# ina219.net
KiCad netlist of a schematic drawn in Altium Designer
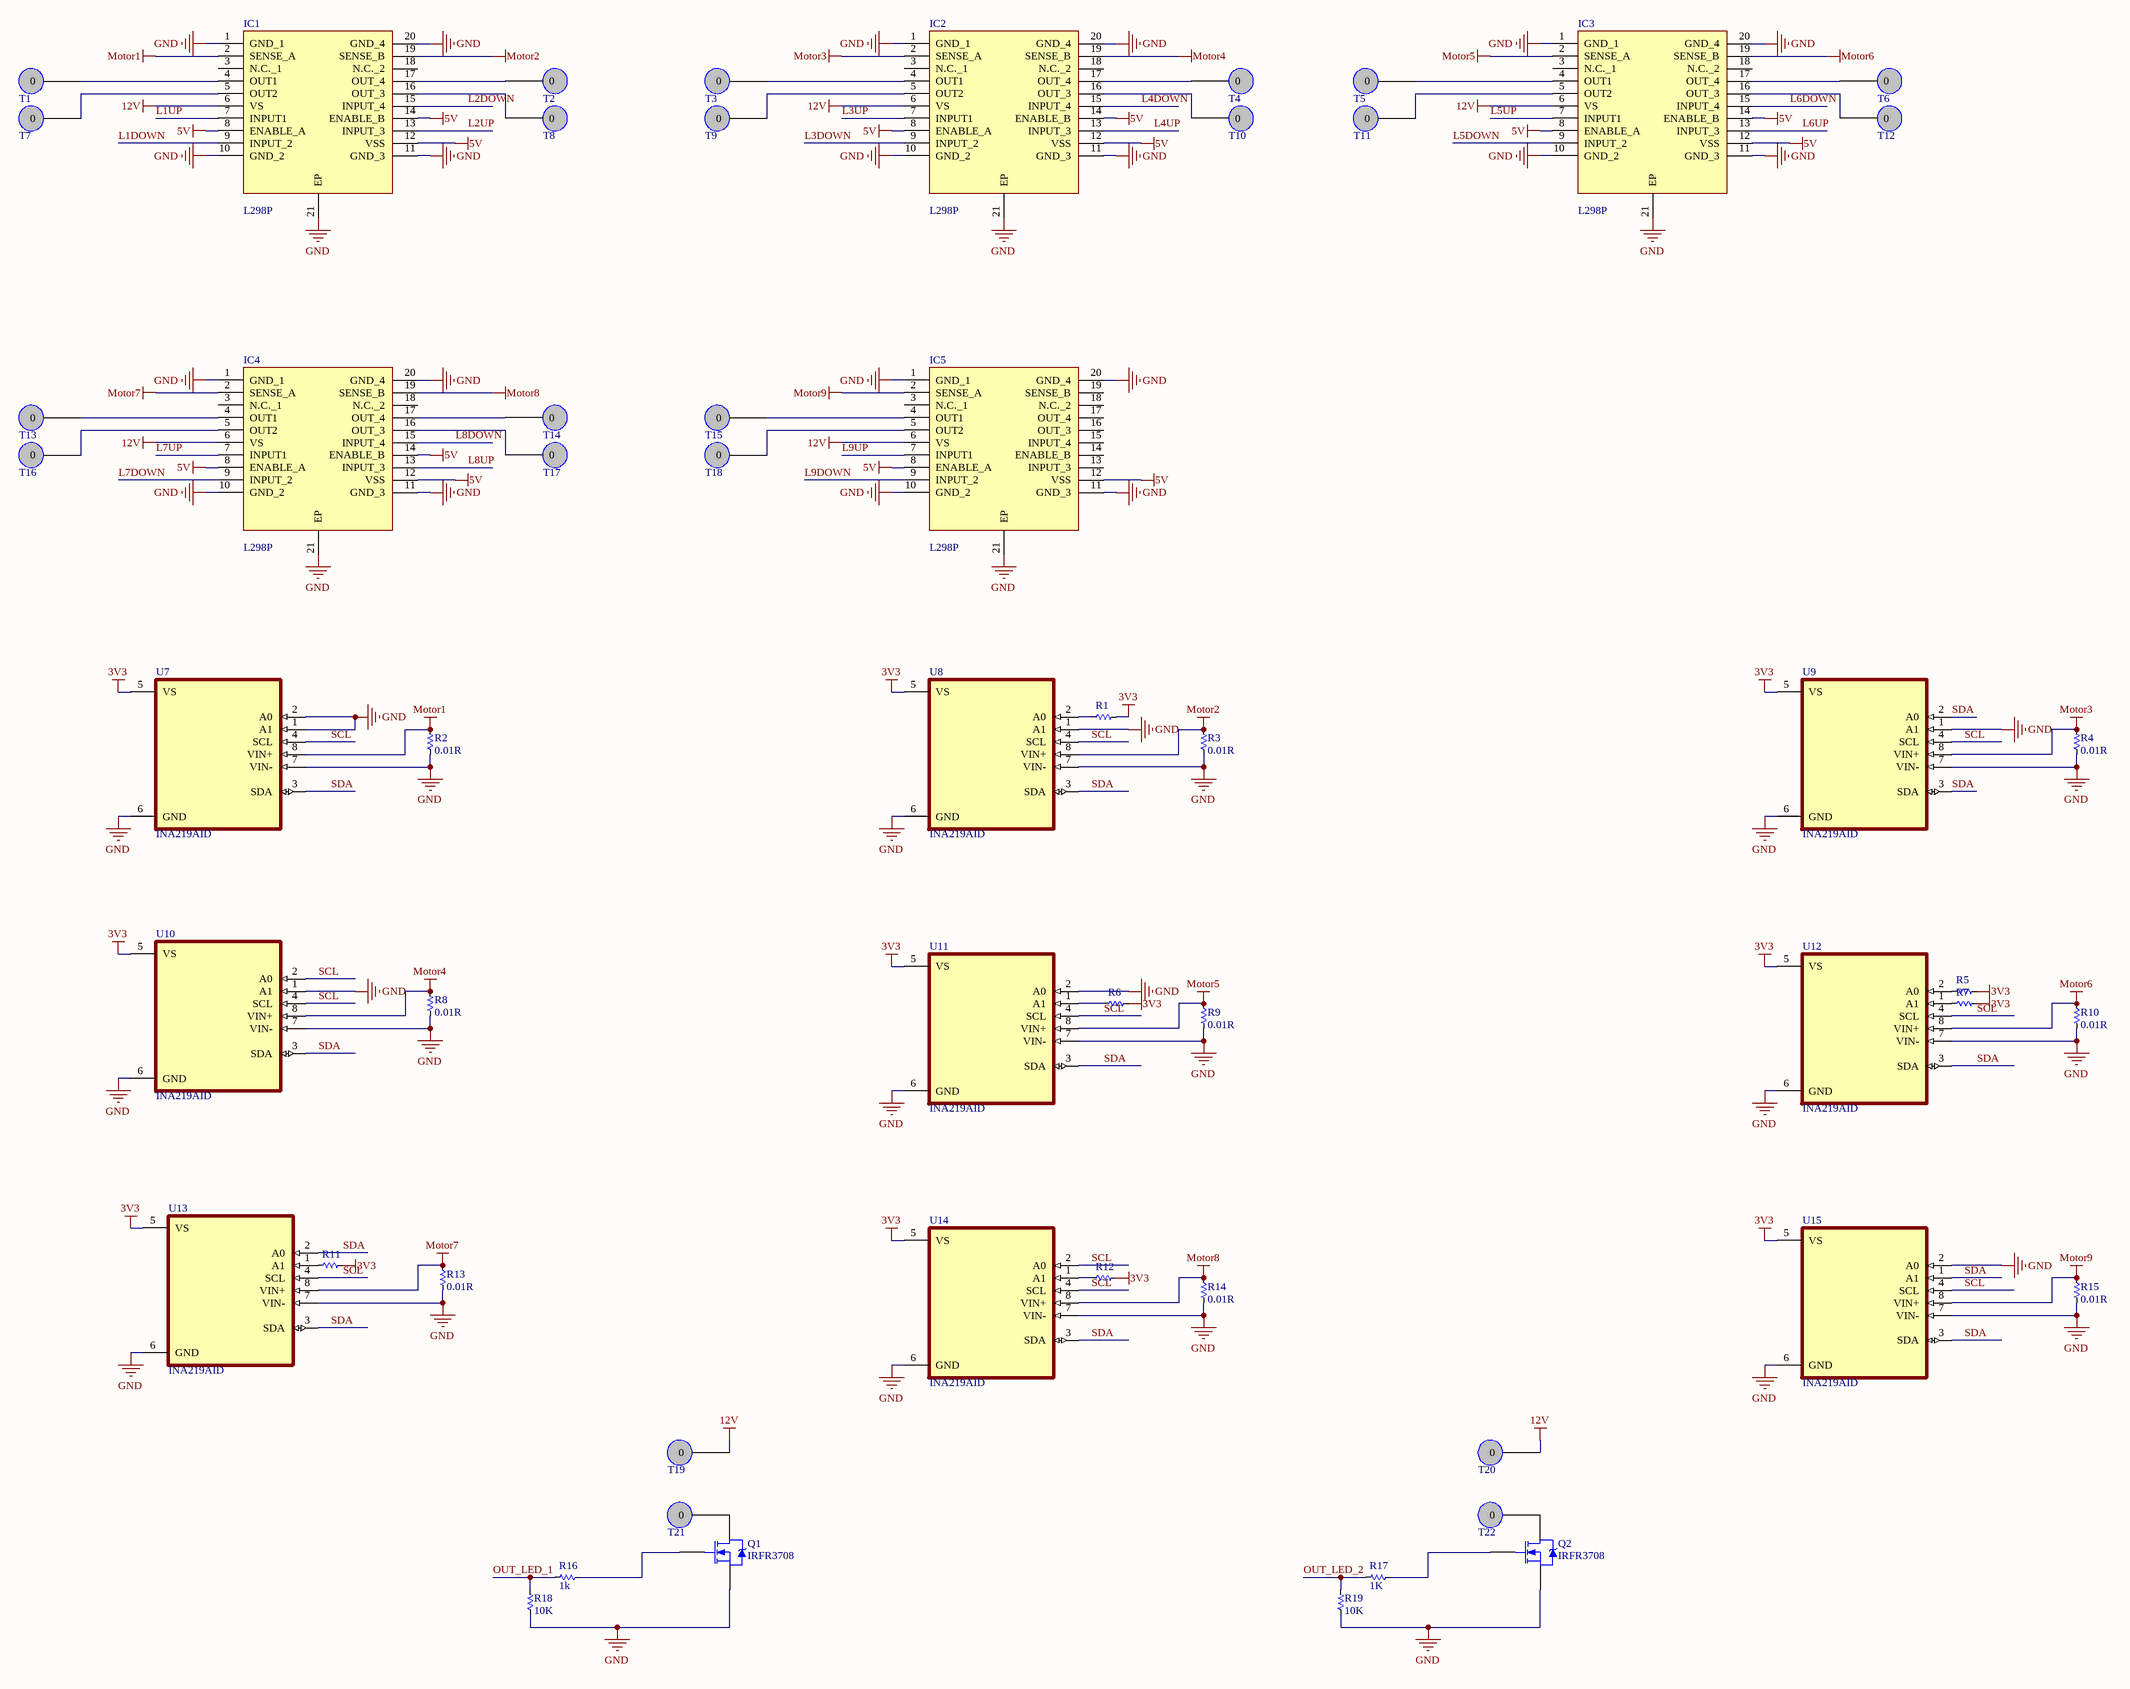
[diagram p0: ina219.SchDoc]

(export (version "E")
  (design (tool "Eeschema 10.0.6"))
  (components
    (comp (ref "IC1")
      (value "L298P")
      (footprint "SamacSys:SOIC127P1420X360-21N")
      (description "Integrated Circuit")
      (fields (field (name "MOUSER PART NUMBER") "511-L298P"))
      (libsource (lib "SamacSys") (part "L298P"))
    )
    (comp (ref "IC2")
      (value "L298P")
      (footprint "SamacSys:SOIC127P1420X360-21N")
      (description "Integrated Circuit")
      (fields (field (name "MOUSER PART NUMBER") "511-L298P"))
      (libsource (lib "SamacSys") (part "L298P"))
    )
    (comp (ref "IC3")
      (value "L298P")
      (footprint "SamacSys:SOIC127P1420X360-21N")
      (description "Integrated Circuit")
      (fields (field (name "MOUSER PART NUMBER") "511-L298P"))
      (libsource (lib "SamacSys") (part "L298P"))
    )
    (comp (ref "IC4")
      (value "L298P")
      (footprint "SamacSys:SOIC127P1420X360-21N")
      (description "Integrated Circuit")
      (fields (field (name "MOUSER PART NUMBER") "511-L298P"))
      (libsource (lib "SamacSys") (part "L298P"))
    )
    (comp (ref "IC5")
      (value "L298P")
      (footprint "SamacSys:SOIC127P1420X360-21N")
      (description "Integrated Circuit")
      (fields (field (name "MOUSER PART NUMBER") "511-L298P"))
      (libsource (lib "SamacSys") (part "L298P"))
    )
    (comp (ref "Q1")
      (value "IRFR3708")
      (footprint "TO-252AA_M")
      (description "HEXFET Power MOSFET")
      (fields (field (name "PUBLISHER") "Altium Limited"))
      (libsource (lib "IR Discrete MOSFET - Power") (part "IRFR3910"))
    )
    (comp (ref "Q2")
      (value "IRFR3708")
      (footprint "TO-252AA_M")
      (description "HEXFET Power MOSFET")
      (fields (field (name "PUBLISHER") "Altium Limited"))
      (libsource (lib "IR Discrete MOSFET - Power") (part "IRFR3910"))
    )
    (comp (ref "R1")
      (value "Res")
      (footprint "RES-SMD-0603")
      (description "Resistor")
      (fields
        (field (name "MANUFACTURER") "Generic Components")
        (field (name "PUBLISHER") "Altium Hobart Technology Centre")
      )
      (libsource (lib "LIBRARY") (part "Res-SMD"))
    )
    (comp (ref "R2")
      (value "0.01R")
      (footprint "RES-SMD-2512")
      (description "Resistor")
      (fields
        (field (name "MANUFACTURER") "Generic Components")
        (field (name "PUBLISHER") "Altium Hobart Technology Centre")
      )
      (libsource (lib "LIBRARY") (part "Res-SMD"))
    )
    (comp (ref "R3")
      (value "0.01R")
      (footprint "RES-SMD-2512")
      (description "Resistor")
      (fields
        (field (name "MANUFACTURER") "Generic Components")
        (field (name "PUBLISHER") "Altium Hobart Technology Centre")
      )
      (libsource (lib "LIBRARY") (part "Res-SMD"))
    )
    (comp (ref "R4")
      (value "0.01R")
      (footprint "RES-SMD-2512")
      (description "Resistor")
      (fields
        (field (name "MANUFACTURER") "Generic Components")
        (field (name "PUBLISHER") "Altium Hobart Technology Centre")
      )
      (libsource (lib "LIBRARY") (part "Res-SMD"))
    )
    (comp (ref "R5")
      (value "Res")
      (footprint "RES-SMD-0603")
      (description "Resistor")
      (fields
        (field (name "MANUFACTURER") "Generic Components")
        (field (name "PUBLISHER") "Altium Hobart Technology Centre")
      )
      (libsource (lib "LIBRARY") (part "Res-SMD"))
    )
    (comp (ref "R6")
      (value "Res")
      (footprint "RES-SMD-0603")
      (description "Resistor")
      (fields
        (field (name "MANUFACTURER") "Generic Components")
        (field (name "PUBLISHER") "Altium Hobart Technology Centre")
      )
      (libsource (lib "LIBRARY") (part "Res-SMD"))
    )
    (comp (ref "R7")
      (value "Res")
      (footprint "RES-SMD-0603")
      (description "Resistor")
      (fields
        (field (name "MANUFACTURER") "Generic Components")
        (field (name "PUBLISHER") "Altium Hobart Technology Centre")
      )
      (libsource (lib "LIBRARY") (part "Res-SMD"))
    )
    (comp (ref "R8")
      (value "0.01R")
      (footprint "RES-SMD-2512")
      (description "Resistor")
      (fields
        (field (name "MANUFACTURER") "Generic Components")
        (field (name "PUBLISHER") "Altium Hobart Technology Centre")
      )
      (libsource (lib "LIBRARY") (part "Res-SMD"))
    )
    (comp (ref "R9")
      (value "0.01R")
      (footprint "RES-SMD-2512")
      (description "Resistor")
      (fields
        (field (name "MANUFACTURER") "Generic Components")
        (field (name "PUBLISHER") "Altium Hobart Technology Centre")
      )
      (libsource (lib "LIBRARY") (part "Res-SMD"))
    )
    (comp (ref "R10")
      (value "0.01R")
      (footprint "RES-SMD-2512")
      (description "Resistor")
      (fields
        (field (name "MANUFACTURER") "Generic Components")
        (field (name "PUBLISHER") "Altium Hobart Technology Centre")
      )
      (libsource (lib "LIBRARY") (part "Res-SMD"))
    )
    (comp (ref "R11")
      (value "Res")
      (footprint "RES-SMD-0603")
      (description "Resistor")
      (fields
        (field (name "MANUFACTURER") "Generic Components")
        (field (name "PUBLISHER") "Altium Hobart Technology Centre")
      )
      (libsource (lib "LIBRARY") (part "Res-SMD"))
    )
    (comp (ref "R12")
      (value "Res")
      (footprint "RES-SMD-0603")
      (description "Resistor")
      (fields
        (field (name "MANUFACTURER") "Generic Components")
        (field (name "PUBLISHER") "Altium Hobart Technology Centre")
      )
      (libsource (lib "LIBRARY") (part "Res-SMD"))
    )
    (comp (ref "R13")
      (value "0.01R")
      (footprint "RES-SMD-2512")
      (description "Resistor")
      (fields
        (field (name "MANUFACTURER") "Generic Components")
        (field (name "PUBLISHER") "Altium Hobart Technology Centre")
      )
      (libsource (lib "LIBRARY") (part "Res-SMD"))
    )
    (comp (ref "R14")
      (value "0.01R")
      (footprint "RES-SMD-2512")
      (description "Resistor")
      (fields
        (field (name "MANUFACTURER") "Generic Components")
        (field (name "PUBLISHER") "Altium Hobart Technology Centre")
      )
      (libsource (lib "LIBRARY") (part "Res-SMD"))
    )
    (comp (ref "R15")
      (value "0.01R")
      (footprint "RES-SMD-2512")
      (description "Resistor")
      (fields
        (field (name "MANUFACTURER") "Generic Components")
        (field (name "PUBLISHER") "Altium Hobart Technology Centre")
      )
      (libsource (lib "LIBRARY") (part "Res-SMD"))
    )
    (comp (ref "R16")
      (value "1k")
      (footprint "RES-SMD-0603")
      (description "Resistor")
      (fields
        (field (name "MANUFACTURER") "Generic Components")
        (field (name "PUBLISHER") "Altium Hobart Technology Centre")
      )
      (libsource (lib "LIBRARY") (part "Res-SMD"))
    )
    (comp (ref "R17")
      (value "1K")
      (footprint "RES-SMD-0603")
      (description "Resistor")
      (fields
        (field (name "MANUFACTURER") "Generic Components")
        (field (name "PUBLISHER") "Altium Hobart Technology Centre")
      )
      (libsource (lib "LIBRARY") (part "Res-SMD"))
    )
    (comp (ref "R18")
      (value "10K")
      (footprint "RES-SMD-0603")
      (description "Resistor")
      (fields
        (field (name "MANUFACTURER") "Generic Components")
        (field (name "PUBLISHER") "Altium Hobart Technology Centre")
      )
      (libsource (lib "LIBRARY") (part "Res-SMD"))
    )
    (comp (ref "R19")
      (value "10K")
      (footprint "RES-SMD-0603")
      (description "Resistor")
      (fields
        (field (name "MANUFACTURER") "Generic Components")
        (field (name "PUBLISHER") "Altium Hobart Technology Centre")
      )
      (libsource (lib "LIBRARY") (part "Res-SMD"))
    )
    (comp (ref "T1")
      (value "Pad")
      (footprint "pad_ina:PCBComponent_1")
      (description "pad")
      (libsource (lib "pad_ina") (part "Component_1"))
    )
    (comp (ref "T2")
      (value "Pad")
      (footprint "pad_ina:PCBComponent_1")
      (description "pad")
      (libsource (lib "pad_ina") (part "Component_1"))
    )
    (comp (ref "T3")
      (value "Pad")
      (footprint "pad_ina:PCBComponent_1")
      (description "pad")
      (libsource (lib "pad_ina") (part "Component_1"))
    )
    (comp (ref "T4")
      (value "Pad")
      (footprint "pad_ina:PCBComponent_1")
      (description "pad")
      (libsource (lib "pad_ina") (part "Component_1"))
    )
    (comp (ref "T5")
      (value "Pad")
      (footprint "pad_ina:PCBComponent_1")
      (description "pad")
      (libsource (lib "pad_ina") (part "Component_1"))
    )
    (comp (ref "T6")
      (value "Pad")
      (footprint "pad_ina:PCBComponent_1")
      (description "pad")
      (libsource (lib "pad_ina") (part "Component_1"))
    )
    (comp (ref "T7")
      (value "Pad")
      (footprint "pad_ina:PCBComponent_1")
      (description "pad")
      (libsource (lib "pad_ina") (part "Component_1"))
    )
    (comp (ref "T8")
      (value "Pad")
      (footprint "pad_ina:PCBComponent_1")
      (description "pad")
      (libsource (lib "pad_ina") (part "Component_1"))
    )
    (comp (ref "T9")
      (value "Pad")
      (footprint "pad_ina:PCBComponent_1")
      (description "pad")
      (libsource (lib "pad_ina") (part "Component_1"))
    )
    (comp (ref "T10")
      (value "Pad")
      (footprint "pad_ina:PCBComponent_1")
      (description "pad")
      (libsource (lib "pad_ina") (part "Component_1"))
    )
    (comp (ref "T11")
      (value "Pad")
      (footprint "pad_ina:PCBComponent_1")
      (description "pad")
      (libsource (lib "pad_ina") (part "Component_1"))
    )
    (comp (ref "T12")
      (value "Pad")
      (footprint "pad_ina:PCBComponent_1")
      (description "pad")
      (libsource (lib "pad_ina") (part "Component_1"))
    )
    (comp (ref "T13")
      (value "Pad")
      (footprint "pad_ina:PCBComponent_1")
      (description "pad")
      (libsource (lib "pad_ina") (part "Component_1"))
    )
    (comp (ref "T14")
      (value "Pad")
      (footprint "pad_ina:PCBComponent_1")
      (description "pad")
      (libsource (lib "pad_ina") (part "Component_1"))
    )
    (comp (ref "T15")
      (value "Pad")
      (footprint "pad_ina:PCBComponent_1")
      (description "pad")
      (libsource (lib "pad_ina") (part "Component_1"))
    )
    (comp (ref "T16")
      (value "Pad")
      (footprint "pad_ina:PCBComponent_1")
      (description "pad")
      (libsource (lib "pad_ina") (part "Component_1"))
    )
    (comp (ref "T17")
      (value "Pad")
      (footprint "pad_ina:PCBComponent_1")
      (description "pad")
      (libsource (lib "pad_ina") (part "Component_1"))
    )
    (comp (ref "T18")
      (value "Pad")
      (footprint "pad_ina:PCBComponent_1")
      (description "pad")
      (libsource (lib "pad_ina") (part "Component_1"))
    )
    (comp (ref "T19")
      (value "Pad")
      (footprint "pad_ina:PCBComponent_1")
      (description "pad")
      (libsource (lib "pad_ina") (part "Component_1"))
    )
    (comp (ref "T20")
      (value "Pad")
      (footprint "pad_ina:PCBComponent_1")
      (description "pad")
      (libsource (lib "pad_ina") (part "Component_1"))
    )
    (comp (ref "T21")
      (value "Pad")
      (footprint "pad_ina:PCBComponent_1")
      (description "pad")
      (libsource (lib "pad_ina") (part "Component_1"))
    )
    (comp (ref "T22")
      (value "Pad")
      (footprint "pad_ina:PCBComponent_1")
      (description "pad")
      (libsource (lib "pad_ina") (part "Component_1"))
    )
    (comp (ref "U7")
      (value "INA219AID")
      (footprint "INA219AID:SOIC127P599X175-8N")
      (description "26V, 12-bit, i2c output current/voltage/power monitor 8-SOIC -40 to 125")
      (fields (field (name "MF") "Texas Instruments"))
      (libsource (lib "INA219AID") (part "INA219AID"))
    )
    (comp (ref "U8")
      (value "INA219AID")
      (footprint "INA219AID:SOIC127P599X175-8N")
      (description "26V, 12-bit, i2c output current/voltage/power monitor 8-SOIC -40 to 125")
      (fields (field (name "MF") "Texas Instruments"))
      (libsource (lib "INA219AID") (part "INA219AID"))
    )
    (comp (ref "U9")
      (value "INA219AID")
      (footprint "INA219AID:SOIC127P599X175-8N")
      (description "26V, 12-bit, i2c output current/voltage/power monitor 8-SOIC -40 to 125")
      (fields (field (name "MF") "Texas Instruments"))
      (libsource (lib "INA219AID") (part "INA219AID"))
    )
    (comp (ref "U10")
      (value "INA219AID")
      (footprint "INA219AID:SOIC127P599X175-8N")
      (description "26V, 12-bit, i2c output current/voltage/power monitor 8-SOIC -40 to 125")
      (fields (field (name "MF") "Texas Instruments"))
      (libsource (lib "INA219AID") (part "INA219AID"))
    )
    (comp (ref "U11")
      (value "INA219AID")
      (footprint "INA219AID:SOIC127P599X175-8N")
      (description "26V, 12-bit, i2c output current/voltage/power monitor 8-SOIC -40 to 125")
      (fields (field (name "MF") "Texas Instruments"))
      (libsource (lib "INA219AID") (part "INA219AID"))
    )
    (comp (ref "U12")
      (value "INA219AID")
      (footprint "INA219AID:SOIC127P599X175-8N")
      (description "26V, 12-bit, i2c output current/voltage/power monitor 8-SOIC -40 to 125")
      (fields (field (name "MF") "Texas Instruments"))
      (libsource (lib "INA219AID") (part "INA219AID"))
    )
    (comp (ref "U13")
      (value "INA219AID")
      (footprint "INA219AID:SOIC127P599X175-8N")
      (description "26V, 12-bit, i2c output current/voltage/power monitor 8-SOIC -40 to 125")
      (fields (field (name "MF") "Texas Instruments"))
      (libsource (lib "INA219AID") (part "INA219AID"))
    )
    (comp (ref "U14")
      (value "INA219AID")
      (footprint "INA219AID:SOIC127P599X175-8N")
      (description "26V, 12-bit, i2c output current/voltage/power monitor 8-SOIC -40 to 125")
      (fields (field (name "MF") "Texas Instruments"))
      (libsource (lib "INA219AID") (part "INA219AID"))
    )
    (comp (ref "U15")
      (value "INA219AID")
      (footprint "INA219AID:SOIC127P599X175-8N")
      (description "26V, 12-bit, i2c output current/voltage/power monitor 8-SOIC -40 to 125")
      (fields (field (name "MF") "Texas Instruments"))
      (libsource (lib "INA219AID") (part "INA219AID"))
    )
  )
  (nets
    (net (code "1") (name "/L1DOWN") (class "Default")
      (node (ref "IC1") (pin "9") (pinfunction "INPUT_2_9") (pintype "passive"))
    )
    (net (code "2") (name "/L1UP") (class "Default")
      (node (ref "IC1") (pin "7") (pinfunction "INPUT1_7") (pintype "passive"))
    )
    (net (code "3") (name "/L2DOWN") (class "Default")
      (node (ref "IC1") (pin "15") (pinfunction "INPUT_4_15") (pintype "passive"))
    )
    (net (code "4") (name "/L2UP") (class "Default")
      (node (ref "IC1") (pin "13") (pinfunction "INPUT_3_13") (pintype "passive"))
    )
    (net (code "5") (name "/L3DOWN") (class "Default")
      (node (ref "IC2") (pin "9") (pinfunction "INPUT_2_9") (pintype "passive"))
    )
    (net (code "6") (name "/L3UP") (class "Default")
      (node (ref "IC2") (pin "7") (pinfunction "INPUT1_7") (pintype "passive"))
    )
    (net (code "7") (name "/L4DOWN") (class "Default")
      (node (ref "IC2") (pin "15") (pinfunction "INPUT_4_15") (pintype "passive"))
    )
    (net (code "8") (name "/L4UP") (class "Default")
      (node (ref "IC2") (pin "13") (pinfunction "INPUT_3_13") (pintype "passive"))
    )
    (net (code "9") (name "/L5DOWN") (class "Default")
      (node (ref "IC3") (pin "9") (pinfunction "INPUT_2_9") (pintype "passive"))
    )
    (net (code "10") (name "/L5UP") (class "Default")
      (node (ref "IC3") (pin "7") (pinfunction "INPUT1_7") (pintype "passive"))
    )
    (net (code "11") (name "/L6DOWN") (class "Default")
      (node (ref "IC3") (pin "15") (pinfunction "INPUT_4_15") (pintype "passive"))
    )
    (net (code "12") (name "/L6UP") (class "Default")
      (node (ref "IC3") (pin "13") (pinfunction "INPUT_3_13") (pintype "passive"))
    )
    (net (code "13") (name "/L7DOWN") (class "Default")
      (node (ref "IC4") (pin "9") (pinfunction "INPUT_2_9") (pintype "passive"))
    )
    (net (code "14") (name "/L7UP") (class "Default")
      (node (ref "IC4") (pin "7") (pinfunction "INPUT1_7") (pintype "passive"))
    )
    (net (code "15") (name "/L8DOWN") (class "Default")
      (node (ref "IC4") (pin "15") (pinfunction "INPUT_4_15") (pintype "passive"))
    )
    (net (code "16") (name "/L8UP") (class "Default")
      (node (ref "IC4") (pin "13") (pinfunction "INPUT_3_13") (pintype "passive"))
    )
    (net (code "17") (name "/L9DOWN") (class "Default")
      (node (ref "IC5") (pin "9") (pinfunction "INPUT_2_9") (pintype "passive"))
    )
    (net (code "18") (name "/L9UP") (class "Default")
      (node (ref "IC5") (pin "7") (pinfunction "INPUT1_7") (pintype "passive"))
    )
    (net (code "19") (name "/OUT_LED_1") (class "Default")
      (node (ref "R16") (pin "1") (pinfunction "1_1") (pintype "passive"))
      (node (ref "R18") (pin "1") (pinfunction "1_1") (pintype "passive"))
    )
    (net (code "20") (name "/OUT_LED_2") (class "Default")
      (node (ref "R17") (pin "1") (pinfunction "1_1") (pintype "passive"))
      (node (ref "R19") (pin "1") (pinfunction "1_1") (pintype "passive"))
    )
    (net (code "21") (name "/SCL") (class "Default")
      (node (ref "U10") (pin "2") (pinfunction "A0_2") (pintype "input"))
      (node (ref "U10") (pin "4") (pinfunction "SCL_4") (pintype "input"))
      (node (ref "U11") (pin "4") (pinfunction "SCL_4") (pintype "input"))
      (node (ref "U12") (pin "4") (pinfunction "SCL_4") (pintype "input"))
      (node (ref "U13") (pin "4") (pinfunction "SCL_4") (pintype "input"))
      (node (ref "U14") (pin "2") (pinfunction "A0_2") (pintype "input"))
      (node (ref "U14") (pin "4") (pinfunction "SCL_4") (pintype "input"))
      (node (ref "U15") (pin "4") (pinfunction "SCL_4") (pintype "input"))
      (node (ref "U7") (pin "4") (pinfunction "SCL_4") (pintype "input"))
      (node (ref "U8") (pin "4") (pinfunction "SCL_4") (pintype "input"))
      (node (ref "U9") (pin "4") (pinfunction "SCL_4") (pintype "input"))
    )
    (net (code "22") (name "/SDA") (class "Default")
      (node (ref "U10") (pin "3") (pinfunction "SDA_3") (pintype "bidirectional"))
      (node (ref "U11") (pin "3") (pinfunction "SDA_3") (pintype "bidirectional"))
      (node (ref "U12") (pin "3") (pinfunction "SDA_3") (pintype "bidirectional"))
      (node (ref "U13") (pin "2") (pinfunction "A0_2") (pintype "input"))
      (node (ref "U13") (pin "3") (pinfunction "SDA_3") (pintype "bidirectional"))
      (node (ref "U14") (pin "3") (pinfunction "SDA_3") (pintype "bidirectional"))
      (node (ref "U15") (pin "1") (pinfunction "A1_1") (pintype "input"))
      (node (ref "U15") (pin "3") (pinfunction "SDA_3") (pintype "bidirectional"))
      (node (ref "U7") (pin "3") (pinfunction "SDA_3") (pintype "bidirectional"))
      (node (ref "U8") (pin "3") (pinfunction "SDA_3") (pintype "bidirectional"))
      (node (ref "U9") (pin "2") (pinfunction "A0_2") (pintype "input"))
      (node (ref "U9") (pin "3") (pinfunction "SDA_3") (pintype "bidirectional"))
    )
    (net (code "23") (name "3V3") (class "Default")
      (node (ref "R1") (pin "1") (pinfunction "1_1") (pintype "passive"))
      (node (ref "R11") (pin "1") (pinfunction "1_1") (pintype "passive"))
      (node (ref "R12") (pin "1") (pinfunction "1_1") (pintype "passive"))
      (node (ref "R5") (pin "1") (pinfunction "1_1") (pintype "passive"))
      (node (ref "R6") (pin "1") (pinfunction "1_1") (pintype "passive"))
      (node (ref "R7") (pin "1") (pinfunction "1_1") (pintype "passive"))
      (node (ref "U10") (pin "5") (pinfunction "VS_5") (pintype "power_in"))
      (node (ref "U11") (pin "5") (pinfunction "VS_5") (pintype "power_in"))
      (node (ref "U12") (pin "5") (pinfunction "VS_5") (pintype "power_in"))
      (node (ref "U13") (pin "5") (pinfunction "VS_5") (pintype "power_in"))
      (node (ref "U14") (pin "5") (pinfunction "VS_5") (pintype "power_in"))
      (node (ref "U15") (pin "5") (pinfunction "VS_5") (pintype "power_in"))
      (node (ref "U7") (pin "5") (pinfunction "VS_5") (pintype "power_in"))
      (node (ref "U8") (pin "5") (pinfunction "VS_5") (pintype "power_in"))
      (node (ref "U9") (pin "5") (pinfunction "VS_5") (pintype "power_in"))
    )
    (net (code "24") (name "5V") (class "Default")
      (node (ref "IC1") (pin "12") (pinfunction "VSS_12") (pintype "passive"))
      (node (ref "IC1") (pin "14") (pinfunction "ENABLE_B_14") (pintype "passive"))
      (node (ref "IC1") (pin "8") (pinfunction "ENABLE_A_8") (pintype "passive"))
      (node (ref "IC2") (pin "12") (pinfunction "VSS_12") (pintype "passive"))
      (node (ref "IC2") (pin "14") (pinfunction "ENABLE_B_14") (pintype "passive"))
      (node (ref "IC2") (pin "8") (pinfunction "ENABLE_A_8") (pintype "passive"))
      (node (ref "IC3") (pin "12") (pinfunction "VSS_12") (pintype "passive"))
      (node (ref "IC3") (pin "14") (pinfunction "ENABLE_B_14") (pintype "passive"))
      (node (ref "IC3") (pin "8") (pinfunction "ENABLE_A_8") (pintype "passive"))
      (node (ref "IC4") (pin "12") (pinfunction "VSS_12") (pintype "passive"))
      (node (ref "IC4") (pin "14") (pinfunction "ENABLE_B_14") (pintype "passive"))
      (node (ref "IC4") (pin "8") (pinfunction "ENABLE_A_8") (pintype "passive"))
      (node (ref "IC5") (pin "12") (pinfunction "VSS_12") (pintype "passive"))
      (node (ref "IC5") (pin "8") (pinfunction "ENABLE_A_8") (pintype "passive"))
    )
    (net (code "25") (name "12V") (class "Default")
      (node (ref "IC1") (pin "6") (pinfunction "VS_6") (pintype "passive"))
      (node (ref "IC2") (pin "6") (pinfunction "VS_6") (pintype "passive"))
      (node (ref "IC3") (pin "6") (pinfunction "VS_6") (pintype "passive"))
      (node (ref "IC4") (pin "6") (pinfunction "VS_6") (pintype "passive"))
      (node (ref "IC5") (pin "6") (pinfunction "VS_6") (pintype "passive"))
      (node (ref "T19") (pin "0") (pinfunction "0_0") (pintype "passive"))
      (node (ref "T20") (pin "0") (pinfunction "0_0") (pintype "passive"))
    )
    (net (code "26") (name "GND") (class "Default")
      (node (ref "IC1") (pin "1") (pinfunction "GND_1_1") (pintype "passive"))
      (node (ref "IC1") (pin "10") (pinfunction "GND_2_10") (pintype "passive"))
      (node (ref "IC1") (pin "11") (pinfunction "GND_3_11") (pintype "passive"))
      (node (ref "IC1") (pin "20") (pinfunction "GND_4_20") (pintype "passive"))
      (node (ref "IC1") (pin "21") (pinfunction "EP_21") (pintype "passive"))
      (node (ref "IC2") (pin "1") (pinfunction "GND_1_1") (pintype "passive"))
      (node (ref "IC2") (pin "10") (pinfunction "GND_2_10") (pintype "passive"))
      (node (ref "IC2") (pin "11") (pinfunction "GND_3_11") (pintype "passive"))
      (node (ref "IC2") (pin "20") (pinfunction "GND_4_20") (pintype "passive"))
      (node (ref "IC2") (pin "21") (pinfunction "EP_21") (pintype "passive"))
      (node (ref "IC3") (pin "1") (pinfunction "GND_1_1") (pintype "passive"))
      (node (ref "IC3") (pin "10") (pinfunction "GND_2_10") (pintype "passive"))
      (node (ref "IC3") (pin "11") (pinfunction "GND_3_11") (pintype "passive"))
      (node (ref "IC3") (pin "20") (pinfunction "GND_4_20") (pintype "passive"))
      (node (ref "IC3") (pin "21") (pinfunction "EP_21") (pintype "passive"))
      (node (ref "IC4") (pin "1") (pinfunction "GND_1_1") (pintype "passive"))
      (node (ref "IC4") (pin "10") (pinfunction "GND_2_10") (pintype "passive"))
      (node (ref "IC4") (pin "11") (pinfunction "GND_3_11") (pintype "passive"))
      (node (ref "IC4") (pin "20") (pinfunction "GND_4_20") (pintype "passive"))
      (node (ref "IC4") (pin "21") (pinfunction "EP_21") (pintype "passive"))
      (node (ref "IC5") (pin "1") (pinfunction "GND_1_1") (pintype "passive"))
      (node (ref "IC5") (pin "10") (pinfunction "GND_2_10") (pintype "passive"))
      (node (ref "IC5") (pin "11") (pinfunction "GND_3_11") (pintype "passive"))
      (node (ref "IC5") (pin "20") (pinfunction "GND_4_20") (pintype "passive"))
      (node (ref "IC5") (pin "21") (pinfunction "EP_21") (pintype "passive"))
      (node (ref "Q1") (pin "3") (pinfunction "S_3") (pintype "passive"))
      (node (ref "Q2") (pin "3") (pinfunction "S_3") (pintype "passive"))
      (node (ref "R10") (pin "2") (pinfunction "2_2") (pintype "passive"))
      (node (ref "R13") (pin "2") (pinfunction "2_2") (pintype "passive"))
      (node (ref "R14") (pin "2") (pinfunction "2_2") (pintype "passive"))
      (node (ref "R15") (pin "2") (pinfunction "2_2") (pintype "passive"))
      (node (ref "R18") (pin "2") (pinfunction "2_2") (pintype "passive"))
      (node (ref "R19") (pin "2") (pinfunction "2_2") (pintype "passive"))
      (node (ref "R2") (pin "2") (pinfunction "2_2") (pintype "passive"))
      (node (ref "R3") (pin "2") (pinfunction "2_2") (pintype "passive"))
      (node (ref "R4") (pin "2") (pinfunction "2_2") (pintype "passive"))
      (node (ref "R8") (pin "2") (pinfunction "2_2") (pintype "passive"))
      (node (ref "R9") (pin "2") (pinfunction "2_2") (pintype "passive"))
      (node (ref "U10") (pin "1") (pinfunction "A1_1") (pintype "input"))
      (node (ref "U10") (pin "6") (pinfunction "GND_6") (pintype "power_in"))
      (node (ref "U10") (pin "7") (pinfunction "VIN-_7") (pintype "input"))
      (node (ref "U11") (pin "2") (pinfunction "A0_2") (pintype "input"))
      (node (ref "U11") (pin "6") (pinfunction "GND_6") (pintype "power_in"))
      (node (ref "U11") (pin "7") (pinfunction "VIN-_7") (pintype "input"))
      (node (ref "U12") (pin "6") (pinfunction "GND_6") (pintype "power_in"))
      (node (ref "U12") (pin "7") (pinfunction "VIN-_7") (pintype "input"))
      (node (ref "U13") (pin "6") (pinfunction "GND_6") (pintype "power_in"))
      (node (ref "U13") (pin "7") (pinfunction "VIN-_7") (pintype "input"))
      (node (ref "U14") (pin "6") (pinfunction "GND_6") (pintype "power_in"))
      (node (ref "U14") (pin "7") (pinfunction "VIN-_7") (pintype "input"))
      (node (ref "U15") (pin "2") (pinfunction "A0_2") (pintype "input"))
      (node (ref "U15") (pin "6") (pinfunction "GND_6") (pintype "power_in"))
      (node (ref "U15") (pin "7") (pinfunction "VIN-_7") (pintype "input"))
      (node (ref "U7") (pin "1") (pinfunction "A1_1") (pintype "input"))
      (node (ref "U7") (pin "2") (pinfunction "A0_2") (pintype "input"))
      (node (ref "U7") (pin "6") (pinfunction "GND_6") (pintype "power_in"))
      (node (ref "U7") (pin "7") (pinfunction "VIN-_7") (pintype "input"))
      (node (ref "U8") (pin "1") (pinfunction "A1_1") (pintype "input"))
      (node (ref "U8") (pin "6") (pinfunction "GND_6") (pintype "power_in"))
      (node (ref "U8") (pin "7") (pinfunction "VIN-_7") (pintype "input"))
      (node (ref "U9") (pin "1") (pinfunction "A1_1") (pintype "input"))
      (node (ref "U9") (pin "6") (pinfunction "GND_6") (pintype "power_in"))
      (node (ref "U9") (pin "7") (pinfunction "VIN-_7") (pintype "input"))
    )
    (net (code "27") (name "Motor1") (class "Default")
      (node (ref "IC1") (pin "2") (pinfunction "SENSE_A_2") (pintype "passive"))
      (node (ref "R2") (pin "1") (pinfunction "1_1") (pintype "passive"))
      (node (ref "U7") (pin "8") (pinfunction "VIN+_8") (pintype "input"))
    )
    (net (code "28") (name "Motor2") (class "Default")
      (node (ref "IC1") (pin "19") (pinfunction "SENSE_B_19") (pintype "passive"))
      (node (ref "R3") (pin "1") (pinfunction "1_1") (pintype "passive"))
      (node (ref "U8") (pin "8") (pinfunction "VIN+_8") (pintype "input"))
    )
    (net (code "29") (name "Motor3") (class "Default")
      (node (ref "IC2") (pin "2") (pinfunction "SENSE_A_2") (pintype "passive"))
      (node (ref "R4") (pin "1") (pinfunction "1_1") (pintype "passive"))
      (node (ref "U9") (pin "8") (pinfunction "VIN+_8") (pintype "input"))
    )
    (net (code "30") (name "Motor4") (class "Default")
      (node (ref "IC2") (pin "19") (pinfunction "SENSE_B_19") (pintype "passive"))
      (node (ref "R8") (pin "1") (pinfunction "1_1") (pintype "passive"))
      (node (ref "U10") (pin "8") (pinfunction "VIN+_8") (pintype "input"))
    )
    (net (code "31") (name "Motor5") (class "Default")
      (node (ref "IC3") (pin "2") (pinfunction "SENSE_A_2") (pintype "passive"))
      (node (ref "R9") (pin "1") (pinfunction "1_1") (pintype "passive"))
      (node (ref "U11") (pin "8") (pinfunction "VIN+_8") (pintype "input"))
    )
    (net (code "32") (name "Motor6") (class "Default")
      (node (ref "IC3") (pin "19") (pinfunction "SENSE_B_19") (pintype "passive"))
      (node (ref "R10") (pin "1") (pinfunction "1_1") (pintype "passive"))
      (node (ref "U12") (pin "8") (pinfunction "VIN+_8") (pintype "input"))
    )
    (net (code "33") (name "Motor7") (class "Default")
      (node (ref "IC4") (pin "2") (pinfunction "SENSE_A_2") (pintype "passive"))
      (node (ref "R13") (pin "1") (pinfunction "1_1") (pintype "passive"))
      (node (ref "U13") (pin "8") (pinfunction "VIN+_8") (pintype "input"))
    )
    (net (code "34") (name "Motor8") (class "Default")
      (node (ref "IC4") (pin "19") (pinfunction "SENSE_B_19") (pintype "passive"))
      (node (ref "R14") (pin "1") (pinfunction "1_1") (pintype "passive"))
      (node (ref "U14") (pin "8") (pinfunction "VIN+_8") (pintype "input"))
    )
    (net (code "35") (name "Motor9") (class "Default")
      (node (ref "IC5") (pin "2") (pinfunction "SENSE_A_2") (pintype "passive"))
      (node (ref "R15") (pin "1") (pinfunction "1_1") (pintype "passive"))
      (node (ref "U15") (pin "8") (pinfunction "VIN+_8") (pintype "input"))
    )
    (net (code "36") (name "Net-(IC1-OUT1)") (class "Default")
      (node (ref "IC1") (pin "4") (pinfunction "OUT1_4") (pintype "passive"))
      (node (ref "T1") (pin "0") (pinfunction "0_0") (pintype "passive"))
    )
    (net (code "37") (name "Net-(IC1-OUT2)") (class "Default")
      (node (ref "IC1") (pin "5") (pinfunction "OUT2_5") (pintype "passive"))
      (node (ref "T7") (pin "0") (pinfunction "0_0") (pintype "passive"))
    )
    (net (code "38") (name "Net-(IC1-OUT_3)") (class "Default")
      (node (ref "IC1") (pin "16") (pinfunction "OUT_3_16") (pintype "passive"))
      (node (ref "T8") (pin "0") (pinfunction "0_0") (pintype "passive"))
    )
    (net (code "39") (name "Net-(IC1-OUT_4)") (class "Default")
      (node (ref "IC1") (pin "17") (pinfunction "OUT_4_17") (pintype "passive"))
      (node (ref "T2") (pin "0") (pinfunction "0_0") (pintype "passive"))
    )
    (net (code "40") (name "Net-(IC2-OUT1)") (class "Default")
      (node (ref "IC2") (pin "4") (pinfunction "OUT1_4") (pintype "passive"))
      (node (ref "T3") (pin "0") (pinfunction "0_0") (pintype "passive"))
    )
    (net (code "41") (name "Net-(IC2-OUT2)") (class "Default")
      (node (ref "IC2") (pin "5") (pinfunction "OUT2_5") (pintype "passive"))
      (node (ref "T9") (pin "0") (pinfunction "0_0") (pintype "passive"))
    )
    (net (code "42") (name "Net-(IC2-OUT_3)") (class "Default")
      (node (ref "IC2") (pin "16") (pinfunction "OUT_3_16") (pintype "passive"))
      (node (ref "T10") (pin "0") (pinfunction "0_0") (pintype "passive"))
    )
    (net (code "43") (name "Net-(IC2-OUT_4)") (class "Default")
      (node (ref "IC2") (pin "17") (pinfunction "OUT_4_17") (pintype "passive"))
      (node (ref "T4") (pin "0") (pinfunction "0_0") (pintype "passive"))
    )
    (net (code "44") (name "Net-(IC3-OUT1)") (class "Default")
      (node (ref "IC3") (pin "4") (pinfunction "OUT1_4") (pintype "passive"))
      (node (ref "T5") (pin "0") (pinfunction "0_0") (pintype "passive"))
    )
    (net (code "45") (name "Net-(IC3-OUT2)") (class "Default")
      (node (ref "IC3") (pin "5") (pinfunction "OUT2_5") (pintype "passive"))
      (node (ref "T11") (pin "0") (pinfunction "0_0") (pintype "passive"))
    )
    (net (code "46") (name "Net-(IC3-OUT_3)") (class "Default")
      (node (ref "IC3") (pin "16") (pinfunction "OUT_3_16") (pintype "passive"))
      (node (ref "T12") (pin "0") (pinfunction "0_0") (pintype "passive"))
    )
    (net (code "47") (name "Net-(IC3-OUT_4)") (class "Default")
      (node (ref "IC3") (pin "17") (pinfunction "OUT_4_17") (pintype "passive"))
      (node (ref "T6") (pin "0") (pinfunction "0_0") (pintype "passive"))
    )
    (net (code "48") (name "Net-(IC4-OUT1)") (class "Default")
      (node (ref "IC4") (pin "4") (pinfunction "OUT1_4") (pintype "passive"))
      (node (ref "T13") (pin "0") (pinfunction "0_0") (pintype "passive"))
    )
    (net (code "49") (name "Net-(IC4-OUT2)") (class "Default")
      (node (ref "IC4") (pin "5") (pinfunction "OUT2_5") (pintype "passive"))
      (node (ref "T16") (pin "0") (pinfunction "0_0") (pintype "passive"))
    )
    (net (code "50") (name "Net-(IC4-OUT_3)") (class "Default")
      (node (ref "IC4") (pin "16") (pinfunction "OUT_3_16") (pintype "passive"))
      (node (ref "T17") (pin "0") (pinfunction "0_0") (pintype "passive"))
    )
    (net (code "51") (name "Net-(IC4-OUT_4)") (class "Default")
      (node (ref "IC4") (pin "17") (pinfunction "OUT_4_17") (pintype "passive"))
      (node (ref "T14") (pin "0") (pinfunction "0_0") (pintype "passive"))
    )
    (net (code "52") (name "Net-(IC5-OUT1)") (class "Default")
      (node (ref "IC5") (pin "4") (pinfunction "OUT1_4") (pintype "passive"))
      (node (ref "T15") (pin "0") (pinfunction "0_0") (pintype "passive"))
    )
    (net (code "53") (name "Net-(IC5-OUT2)") (class "Default")
      (node (ref "IC5") (pin "5") (pinfunction "OUT2_5") (pintype "passive"))
      (node (ref "T18") (pin "0") (pinfunction "0_0") (pintype "passive"))
    )
    (net (code "54") (name "Net-(Q1-D)") (class "Default")
      (node (ref "Q1") (pin "4") (pinfunction "D_4") (pintype "passive"))
      (node (ref "T21") (pin "0") (pinfunction "0_0") (pintype "passive"))
    )
    (net (code "55") (name "Net-(Q1-G)") (class "Default")
      (node (ref "Q1") (pin "1") (pinfunction "G_1") (pintype "passive"))
      (node (ref "R16") (pin "2") (pinfunction "2_2") (pintype "passive"))
    )
    (net (code "56") (name "Net-(Q2-D)") (class "Default")
      (node (ref "Q2") (pin "4") (pinfunction "D_4") (pintype "passive"))
      (node (ref "T22") (pin "0") (pinfunction "0_0") (pintype "passive"))
    )
    (net (code "57") (name "Net-(Q2-G)") (class "Default")
      (node (ref "Q2") (pin "1") (pinfunction "G_1") (pintype "passive"))
      (node (ref "R17") (pin "2") (pinfunction "2_2") (pintype "passive"))
    )
    (net (code "58") (name "Net-(U8-A0)") (class "Default")
      (node (ref "R1") (pin "2") (pinfunction "2_2") (pintype "passive"))
      (node (ref "U8") (pin "2") (pinfunction "A0_2") (pintype "input"))
    )
    (net (code "59") (name "Net-(U11-A1)") (class "Default")
      (node (ref "R6") (pin "2") (pinfunction "2_2") (pintype "passive"))
      (node (ref "U11") (pin "1") (pinfunction "A1_1") (pintype "input"))
    )
    (net (code "60") (name "Net-(U12-A0)") (class "Default")
      (node (ref "R5") (pin "2") (pinfunction "2_2") (pintype "passive"))
      (node (ref "U12") (pin "2") (pinfunction "A0_2") (pintype "input"))
    )
    (net (code "61") (name "Net-(U12-A1)") (class "Default")
      (node (ref "R7") (pin "2") (pinfunction "2_2") (pintype "passive"))
      (node (ref "U12") (pin "1") (pinfunction "A1_1") (pintype "input"))
    )
    (net (code "62") (name "Net-(U13-A1)") (class "Default")
      (node (ref "R11") (pin "2") (pinfunction "2_2") (pintype "passive"))
      (node (ref "U13") (pin "1") (pinfunction "A1_1") (pintype "input"))
    )
    (net (code "63") (name "Net-(U14-A1)") (class "Default")
      (node (ref "R12") (pin "2") (pinfunction "2_2") (pintype "passive"))
      (node (ref "U14") (pin "1") (pinfunction "A1_1") (pintype "input"))
    )
    (net (code "64") (name "unconnected-(IC1-N.C._1-Pad3)") (class "Default")
      (node (ref "IC1") (pin "3") (pinfunction "N.C._1_3") (pintype "passive"))
    )
    (net (code "65") (name "unconnected-(IC1-N.C._2-Pad18)") (class "Default")
      (node (ref "IC1") (pin "18") (pinfunction "N.C._2_18") (pintype "passive"))
    )
    (net (code "66") (name "unconnected-(IC2-N.C._1-Pad3)") (class "Default")
      (node (ref "IC2") (pin "3") (pinfunction "N.C._1_3") (pintype "passive"))
    )
    (net (code "67") (name "unconnected-(IC2-N.C._2-Pad18)") (class "Default")
      (node (ref "IC2") (pin "18") (pinfunction "N.C._2_18") (pintype "passive"))
    )
    (net (code "68") (name "unconnected-(IC3-N.C._1-Pad3)") (class "Default")
      (node (ref "IC3") (pin "3") (pinfunction "N.C._1_3") (pintype "passive"))
    )
    (net (code "69") (name "unconnected-(IC3-N.C._2-Pad18)") (class "Default")
      (node (ref "IC3") (pin "18") (pinfunction "N.C._2_18") (pintype "passive"))
    )
    (net (code "70") (name "unconnected-(IC4-N.C._1-Pad3)") (class "Default")
      (node (ref "IC4") (pin "3") (pinfunction "N.C._1_3") (pintype "passive"))
    )
    (net (code "71") (name "unconnected-(IC4-N.C._2-Pad18)") (class "Default")
      (node (ref "IC4") (pin "18") (pinfunction "N.C._2_18") (pintype "passive"))
    )
    (net (code "72") (name "unconnected-(IC5-ENABLE_B-Pad14)") (class "Default")
      (node (ref "IC5") (pin "14") (pinfunction "ENABLE_B_14") (pintype "passive"))
    )
    (net (code "73") (name "unconnected-(IC5-INPUT_3-Pad13)") (class "Default")
      (node (ref "IC5") (pin "13") (pinfunction "INPUT_3_13") (pintype "passive"))
    )
    (net (code "74") (name "unconnected-(IC5-INPUT_4-Pad15)") (class "Default")
      (node (ref "IC5") (pin "15") (pinfunction "INPUT_4_15") (pintype "passive"))
    )
    (net (code "75") (name "unconnected-(IC5-N.C._1-Pad3)") (class "Default")
      (node (ref "IC5") (pin "3") (pinfunction "N.C._1_3") (pintype "passive"))
    )
    (net (code "76") (name "unconnected-(IC5-N.C._2-Pad18)") (class "Default")
      (node (ref "IC5") (pin "18") (pinfunction "N.C._2_18") (pintype "passive"))
    )
    (net (code "77") (name "unconnected-(IC5-OUT_3-Pad16)") (class "Default")
      (node (ref "IC5") (pin "16") (pinfunction "OUT_3_16") (pintype "passive"))
    )
    (net (code "78") (name "unconnected-(IC5-OUT_4-Pad17)") (class "Default")
      (node (ref "IC5") (pin "17") (pinfunction "OUT_4_17") (pintype "passive"))
    )
    (net (code "79") (name "unconnected-(IC5-SENSE_B-Pad19)") (class "Default")
      (node (ref "IC5") (pin "19") (pinfunction "SENSE_B_19") (pintype "passive"))
    )
  )
)
